# Sheet1.net
KiCad netlist of a schematic drawn in Altium Designer
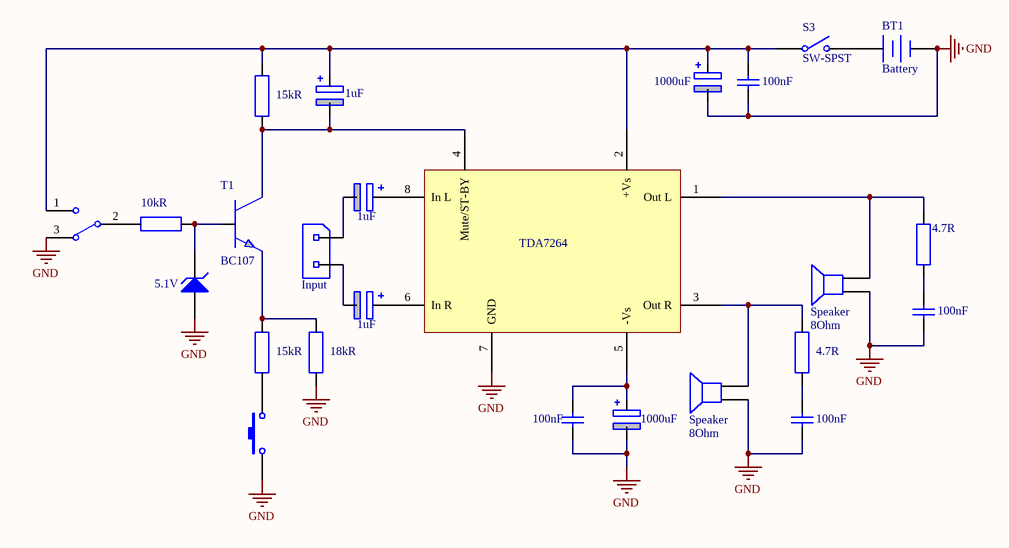
[diagram p0: Sheet1.SchDoc]

(export (version "E")
  (design (tool "Eeschema 10.0.6"))
  (components
    (comp (ref "BT1")
      (value "Battery")
      (footprint "BAT-2")
      (description "Multicell Battery")
      (fields (field (name "PUBLISHER") "Altium Limited"))
      (libsource (lib "Miscellaneous Devices") (part "Battery"))
    )
    (comp (ref "C1")
      (value "1uF")
      (footprint "cap 48 pol (.46/.2/.6/125/36)")
      (description "elektrolytische condensator axiaal 0.47uF/63V")
      (fields (field (name "PART NUMBER") "CECA0.47uF/63V") (field (name "Comment") "Cap"))
      (libsource (lib "CDE_Library") (part "CECA0.47uF/63V"))
    )
    (comp (ref "C2")
      (value "1uF")
      (footprint "cap 48 pol (.46/.2/.6/125/36)")
      (description "elektrolytische condensator axiaal 0.47uF/63V")
      (fields (field (name "PART NUMBER") "CECA0.47uF/63V") (field (name "Comment") "Cap"))
      (libsource (lib "CDE_Library") (part "CECA0.47uF/63V"))
    )
    (comp (ref "C3")
      (value "1uF")
      (footprint "cap 48 pol (.46/.2/.6/125/36)")
      (description "elektrolytische condensator axiaal 0.47uF/63V")
      (fields (field (name "PART NUMBER") "CECA0.47uF/63V") (field (name "Comment") "Cap"))
      (libsource (lib "CDE_Library") (part "CECA0.47uF/63V"))
    )
    (comp (ref "C4")
      (value "1000uF")
      (footprint "cap 48 pol (.46/.2/.6/125/36)")
      (description "elektrolytische condensator axiaal 0.47uF/63V")
      (fields (field (name "PART NUMBER") "CECA0.47uF/63V") (field (name "Comment") "Cap"))
      (libsource (lib "CDE_Library") (part "CECA0.47uF/63V"))
    )
    (comp (ref "C5")
      (value "100nF")
      (footprint "RAD-0.3")
      (description "Capacitor")
      (fields (field (name "PUBLISHER") "Altium Limited"))
      (libsource (lib "Miscellaneous Devices") (part "Cap"))
    )
    (comp (ref "C6")
      (value "1000uF")
      (footprint "cap 48 pol (.46/.2/.6/125/36)")
      (description "elektrolytische condensator axiaal 0.47uF/63V")
      (fields (field (name "PART NUMBER") "CECA0.47uF/63V") (field (name "Comment") "Cap"))
      (libsource (lib "CDE_Library") (part "CECA0.47uF/63V"))
    )
    (comp (ref "C7")
      (value "100nF")
      (footprint "RAD-0.3")
      (description "Capacitor")
      (fields (field (name "Comment") "Cap") (field (name "PUBLISHER") "Altium Limited"))
      (libsource (lib "Miscellaneous Devices") (part "Cap"))
    )
    (comp (ref "C8")
      (value "100nF")
      (footprint "RAD-0.3")
      (description "Capacitor")
      (fields (field (name "Comment") "Cap") (field (name "PUBLISHER") "Altium Limited"))
      (libsource (lib "Miscellaneous Devices") (part "Cap"))
    )
    (comp (ref "C9")
      (value "100nF")
      (footprint "RAD-0.3")
      (description "Capacitor")
      (fields (field (name "Comment") "Cap") (field (name "PUBLISHER") "Altium Limited"))
      (libsource (lib "Miscellaneous Devices") (part "Cap"))
    )
    (comp (ref "D1")
      (value "5.1V")
      (footprint "DIODE-0.7")
      (description "Zener Diode")
      (fields (field (name "Comment") "D Zener") (field (name "PUBLISHER") "Altium Limited"))
      (libsource (lib "Miscellaneous Devices") (part "D Zener"))
    )
    (comp (ref "In")
      (value "Input")
      (footprint "hdr 1x2")
      (description "pcb header recht 1x2  pitch 100mil")
      (fields (field (name "PART NUMBER") "CON HDR 1x2"))
      (libsource (lib "CDE_Library") (part "CON HDR 1x2"))
    )
    (comp (ref "LS_L")
      (value "Speaker")
      (footprint "PIN2")
      (description "Loudspeaker")
      (fields (field (name "INTERNAL RESISTANCE") "8Ohm") (field (name "PUBLISHER") "Altium Limited"))
      (libsource (lib "Miscellaneous Devices") (part "Speaker"))
    )
    (comp (ref "LS_R")
      (value "Speaker")
      (footprint "PIN2")
      (description "Loudspeaker")
      (fields (field (name "INTERNAL RESISTANCE") "8Ohm") (field (name "PUBLISHER") "Altium Limited"))
      (libsource (lib "Miscellaneous Devices") (part "Speaker"))
    )
    (comp (ref "R1")
      (value "10kR")
      (footprint "ws 0.6W H")
      (description "weerstand 0R2 0.6W")
      (fields (field (name "Comment") "Res"))
      (libsource (lib "CDE_Library") (part "0R2"))
    )
    (comp (ref "R2")
      (value "15kR")
      (footprint "ws 0.6W H")
      (description "weerstand 0R2 0.6W")
      (fields (field (name "Comment") "Res"))
      (libsource (lib "CDE_Library") (part "0R2"))
    )
    (comp (ref "R3")
      (value "18kR")
      (footprint "ws 0.6W H")
      (description "weerstand 0R2 0.6W")
      (fields (field (name "Comment") "Res"))
      (libsource (lib "CDE_Library") (part "0R2"))
    )
    (comp (ref "R4")
      (value "15kR")
      (footprint "ws 0.6W H")
      (description "weerstand 0R2 0.6W")
      (fields (field (name "Comment") "Res"))
      (libsource (lib "CDE_Library") (part "0R2"))
    )
    (comp (ref "R5")
      (value "4.7R")
      (footprint "ws 0.6W H")
      (description "weerstand 0R2 0.6W")
      (fields (field (name "Comment") "Res"))
      (libsource (lib "CDE_Library") (part "0R2"))
    )
    (comp (ref "R6")
      (value "4.7R")
      (footprint "ws 0.6W H")
      (description "weerstand 0R2 0.6W")
      (fields (field (name "Comment") "Res"))
      (libsource (lib "CDE_Library") (part "0R2"))
    )
    (comp (ref "S1")
      (value "SW-SPDT")
      (footprint "TL36WW15050")
      (description "SPDT Subminiature Toggle Switch, Right Angle Mounting, Vertical Actuation")
      (fields (field (name "PUBLISHER") "Altium Limited"))
      (libsource (lib "Miscellaneous Devices") (part "SW-SPDT"))
    )
    (comp (ref "S2")
      (value "SW-PB")
      (footprint "SPST-2")
      (description "Switch")
      (fields (field (name "PUBLISHER") "Altium Limited"))
      (libsource (lib "Miscellaneous Devices") (part "SW-PB"))
    )
    (comp (ref "S3")
      (value "SW-SPST")
      (footprint "SPST-2")
      (description "Single-Pole, Single-Throw Switch")
      (fields (field (name "PUBLISHER") "Altium Limited"))
      (libsource (lib "Miscellaneous Devices") (part "SW-SPST"))
    )
    (comp (ref "T1")
      (value "BC107")
      (footprint "TO-18")
      (description "NPN transistor")
      (libsource (lib "CDE_Library") (part "BC107"))
    )
    (comp (ref "TDA7264")
      (value "TDA7264 stereo audio amplifier")
      (footprint "MultiWatt8")
      (description "25 W + 25 W stereo amplifier with mute and standby")
      (libsource (lib "TomSchLib") (part "TDA7264 stereo audio amplifier"))
    )
  )
  (nets
    (net (code "1") (name "GND") (class "Default")
      (node (ref "BT1") (pin "2") (pinfunction "-_2") (pintype "passive"))
      (node (ref "C4") (pin "2") (pintype "passive"))
      (node (ref "C5") (pin "1") (pinfunction "1_1") (pintype "passive"))
      (node (ref "C6") (pin "2") (pintype "passive"))
      (node (ref "C7") (pin "1") (pinfunction "1_1") (pintype "passive"))
      (node (ref "C8") (pin "1") (pinfunction "1_1") (pintype "passive"))
      (node (ref "C9") (pin "1") (pinfunction "1_1") (pintype "passive"))
      (node (ref "D1") (pin "1") (pinfunction "A_1") (pintype "passive"))
      (node (ref "LS_L") (pin "1") (pinfunction "1_1") (pintype "passive"))
      (node (ref "LS_R") (pin "1") (pinfunction "1_1") (pintype "passive"))
      (node (ref "R3") (pin "1") (pintype "passive"))
      (node (ref "S1") (pin "3") (pinfunction "3_3") (pintype "passive"))
      (node (ref "S2") (pin "1") (pinfunction "1_1") (pintype "passive"))
      (node (ref "TDA7264") (pin "7") (pinfunction "GND_7") (pintype "passive"))
    )
    (net (code "2") (name "Net-(BT1-+)") (class "Default")
      (node (ref "BT1") (pin "1") (pinfunction "+_1") (pintype "passive"))
      (node (ref "S3") (pin "2") (pinfunction "NO_2") (pintype "passive"))
    )
    (net (code "3") (name "Net-(C1-Pad2)") (class "Default")
      (node (ref "C1") (pin "2") (pintype "passive"))
      (node (ref "In") (pin "1") (pintype "passive"))
    )
    (net (code "4") (name "Net-(C2-Pad2)") (class "Default")
      (node (ref "C2") (pin "2") (pintype "passive"))
      (node (ref "In") (pin "2") (pintype "passive"))
    )
    (net (code "5") (name "Net-(C8-Pad2)") (class "Default")
      (node (ref "C8") (pin "2") (pinfunction "2_2") (pintype "passive"))
      (node (ref "R5") (pin "2") (pintype "passive"))
    )
    (net (code "6") (name "Net-(C9-Pad2)") (class "Default")
      (node (ref "C9") (pin "2") (pinfunction "2_2") (pintype "passive"))
      (node (ref "R6") (pin "1") (pintype "passive"))
    )
    (net (code "7") (name "Net-(D1-K)") (class "Default")
      (node (ref "D1") (pin "2") (pinfunction "K_2") (pintype "passive"))
      (node (ref "R1") (pin "1") (pintype "passive"))
      (node (ref "T1") (pin "2") (pintype "passive"))
    )
    (net (code "8") (name "Net-(R1-Pad2)") (class "Default")
      (node (ref "R1") (pin "2") (pintype "passive"))
      (node (ref "S1") (pin "2") (pinfunction "2_2") (pintype "passive"))
    )
    (net (code "9") (name "Net-(R3-Pad2)") (class "Default")
      (node (ref "R3") (pin "2") (pintype "passive"))
      (node (ref "R4") (pin "2") (pintype "passive"))
      (node (ref "T1") (pin "1") (pintype "passive"))
    )
    (net (code "10") (name "Net-(R4-Pad1)") (class "Default")
      (node (ref "R4") (pin "1") (pintype "passive"))
      (node (ref "S2") (pin "2") (pinfunction "2_2") (pintype "passive"))
    )
    (net (code "11") (name "Net-(S3-COMMON)") (class "Default")
      (node (ref "C3") (pin "1") (pintype "passive"))
      (node (ref "C4") (pin "1") (pintype "passive"))
      (node (ref "C5") (pin "2") (pinfunction "2_2") (pintype "passive"))
      (node (ref "R2") (pin "2") (pintype "passive"))
      (node (ref "S1") (pin "1") (pinfunction "1_1") (pintype "passive"))
      (node (ref "S3") (pin "1") (pinfunction "COMMON_1") (pintype "passive"))
      (node (ref "TDA7264") (pin "2") (pinfunction "+Vs_2") (pintype "passive"))
    )
    (net (code "12") (name "Net-(TDA7264--Vs)") (class "Default")
      (node (ref "C6") (pin "1") (pintype "passive"))
      (node (ref "C7") (pin "2") (pinfunction "2_2") (pintype "passive"))
      (node (ref "TDA7264") (pin "5") (pinfunction "-Vs_5") (pintype "passive"))
    )
    (net (code "13") (name "Net-(TDA7264-In_L)") (class "Default")
      (node (ref "C1") (pin "1") (pintype "passive"))
      (node (ref "TDA7264") (pin "8") (pinfunction "In_L_8") (pintype "passive"))
    )
    (net (code "14") (name "Net-(TDA7264-In_R)") (class "Default")
      (node (ref "C2") (pin "1") (pintype "passive"))
      (node (ref "TDA7264") (pin "6") (pinfunction "In_R_6") (pintype "passive"))
    )
    (net (code "15") (name "Net-(TDA7264-Mute{slash}ST-BY)") (class "Default")
      (node (ref "C3") (pin "2") (pintype "passive"))
      (node (ref "R2") (pin "1") (pintype "passive"))
      (node (ref "T1") (pin "3") (pintype "passive"))
      (node (ref "TDA7264") (pin "4") (pinfunction "Mute/ST-BY_4") (pintype "passive"))
    )
    (net (code "16") (name "Net-(TDA7264-Out_L)") (class "Default")
      (node (ref "LS_L") (pin "2") (pinfunction "2_2") (pintype "passive"))
      (node (ref "R5") (pin "1") (pintype "passive"))
      (node (ref "TDA7264") (pin "1") (pinfunction "Out_L_1") (pintype "passive"))
    )
    (net (code "17") (name "Net-(TDA7264-Out_R)") (class "Default")
      (node (ref "LS_R") (pin "2") (pinfunction "2_2") (pintype "passive"))
      (node (ref "R6") (pin "2") (pintype "passive"))
      (node (ref "TDA7264") (pin "3") (pinfunction "Out_R_3") (pintype "passive"))
    )
  )
)
